# lion.net
KiCad netlist of a schematic drawn in EAGLE
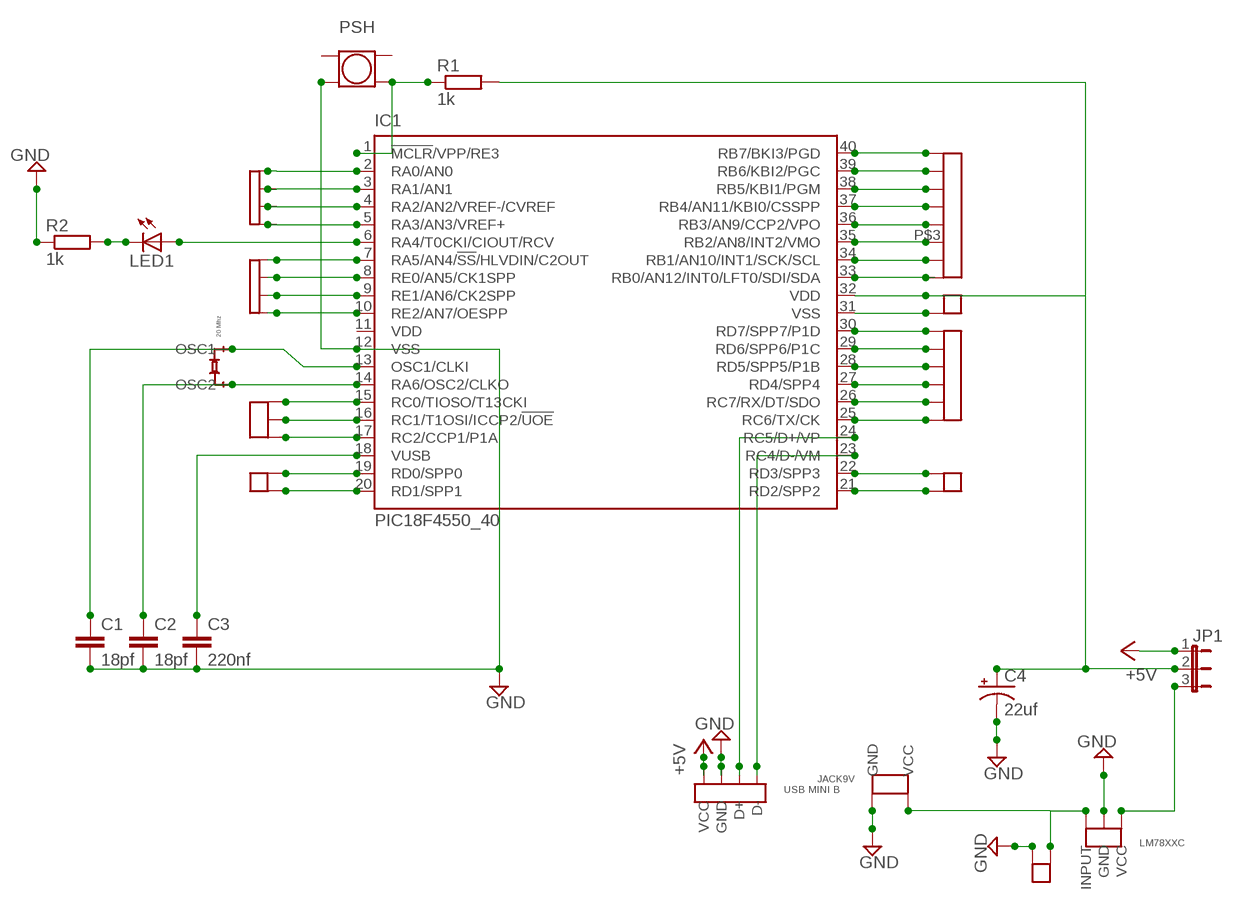
[diagram p0: schematic, sheet 1]

(export (version "E")
  (design (tool "Eeschema 10.0.6"))
  (components
    (comp (ref "BUTTON1")
      (value "PUSHBTN")
      (footprint "eagle-import:PUSHBTN")
      (libsource (lib "eagle-import") (part "PUSHBTN"))
    )
    (comp (ref "C1")
      (value "18pf")
      (footprint "eagle-import:C050-025X075")
      (libsource (lib "eagle-import") (part "C-EU050-025X075"))
    )
    (comp (ref "C2")
      (value "18pf")
      (footprint "eagle-import:C050-025X075")
      (libsource (lib "eagle-import") (part "C-EU050-025X075"))
    )
    (comp (ref "C3")
      (value "220nf")
      (footprint "eagle-import:C050-025X075")
      (libsource (lib "eagle-import") (part "C-EU050-025X075"))
    )
    (comp (ref "C4")
      (value "22uf")
      (footprint "eagle-import:E2,5-6E")
      (libsource (lib "eagle-import") (part "CPOL-USE2,5-6E"))
    )
    (comp (ref "IC1")
      (value "PIC18F4550_40")
      (footprint "eagle-import:DIL40")
      (fields (field (name "MF") "MICROCHIP") (field (name "MPN") "PIC18F4550-I/P"))
      (libsource (lib "eagle-import") (part "PIC18F4_40550"))
    )
    (comp (ref "JACK9V")
      (value "9VJACK")
      (footprint "eagle-import:9VJACK")
      (libsource (lib "eagle-import") (part "9VJACK"))
    )
    (comp (ref "JP1")
      (value "JP2E")
      (footprint "eagle-import:JP2")
      (libsource (lib "eagle-import") (part "JP2E"))
    )
    (comp (ref "LED1")
      (value "LEDLD260")
      (footprint "eagle-import:LD260")
      (libsource (lib "eagle-import") (part "LEDLD260"))
    )
    (comp (ref "R1")
      (value "1k")
      (footprint "eagle-import:0204_7")
      (libsource (lib "eagle-import") (part "R-EU_0204/7"))
    )
    (comp (ref "R2")
      (value "1k")
      (footprint "eagle-import:0204_7")
      (libsource (lib "eagle-import") (part "R-EU_0204/7"))
    )
    (comp (ref "U$1")
      (value "USBMINIB")
      (footprint "eagle-import:USBMINIB")
      (libsource (lib "eagle-import") (part "USBMINIB"))
    )
    (comp (ref "U$2")
      (value "20 Mhz")
      (footprint "eagle-import:CRYSTAL")
      (libsource (lib "eagle-import") (part "CRYSTAL"))
    )
    (comp (ref "U$3")
      (value "DUBOX3")
      (footprint "eagle-import:DUBOX3")
      (libsource (lib "eagle-import") (part "DUBOX3"))
    )
    (comp (ref "U$4")
      (value "DUBOX6")
      (footprint "eagle-import:DUBOX6")
      (libsource (lib "eagle-import") (part "DUBOX6"))
    )
    (comp (ref "U$5")
      (value "DUBOX8")
      (footprint "eagle-import:DUBOX8")
      (libsource (lib "eagle-import") (part "DUBOX8"))
    )
    (comp (ref "U$6")
      (value "DUBOX2")
      (footprint "eagle-import:DUBOX2")
      (libsource (lib "eagle-import") (part "DUBOX2"))
    )
    (comp (ref "U$7")
      (value "DUBOX2")
      (footprint "eagle-import:DUBOX2")
      (libsource (lib "eagle-import") (part "DUBOX2"))
    )
    (comp (ref "U$8")
      (value "DUBOX2")
      (footprint "eagle-import:DUBOX2")
      (libsource (lib "eagle-import") (part "DUBOX2"))
    )
    (comp (ref "U$9")
      (value "DUBOX4")
      (footprint "eagle-import:DUBOX4")
      (libsource (lib "eagle-import") (part "DUBOX4"))
    )
    (comp (ref "U$10")
      (value "DUBOX4")
      (footprint "eagle-import:DUBOX4")
      (libsource (lib "eagle-import") (part "DUBOX4"))
    )
    (comp (ref "U$11")
      (value "LM7805C")
      (footprint "eagle-import:LM7805C")
      (libsource (lib "eagle-import") (part "LM7805C"))
    )
    (comp (ref "U$12")
      (value "DUBOX2")
      (footprint "eagle-import:DUBOX2")
      (libsource (lib "eagle-import") (part "DUBOX2"))
    )
  )
  (nets
    (net (code "1") (name "+5V") (class "Default")
      (node (ref "JP1") (pin "1") (pinfunction "1_1") (pintype "passive"))
      (node (ref "U$1") (pin "VCC") (pinfunction "VCC_VCC") (pintype "power_in"))
    )
    (net (code "2") (name "/VDD") (class "Default")
      (node (ref "IC1") (pin "11") (pinfunction "VDD_11") (pintype "power_in"))
    )
    (net (code "3") (name "GND") (class "Default")
      (node (ref "BUTTON1") (pin "P$2") (pinfunction "P12_P$2") (pintype "bidirectional"))
      (node (ref "C1") (pin "2") (pinfunction "2_2") (pintype "passive"))
      (node (ref "C2") (pin "2") (pinfunction "2_2") (pintype "passive"))
      (node (ref "C3") (pin "2") (pinfunction "2_2") (pintype "passive"))
      (node (ref "C4") (pin "-") (pinfunction "-_-") (pintype "passive"))
      (node (ref "IC1") (pin "12") (pinfunction "VSS_12") (pintype "power_in"))
      (node (ref "JACK9V") (pin "GND") (pinfunction "GND_GND") (pintype "power_in"))
      (node (ref "R2") (pin "1") (pinfunction "1_1") (pintype "passive"))
      (node (ref "U$1") (pin "GND") (pinfunction "GND_GND") (pintype "power_in"))
      (node (ref "U$11") (pin "GND") (pinfunction "GND_GND") (pintype "power_in"))
      (node (ref "U$12") (pin "P$1") (pinfunction "P1_P$1") (pintype "bidirectional"))
    )
    (net (code "4") (name "Net-(BUTTON1-P22)") (class "Default")
      (node (ref "BUTTON1") (pin "P$4") (pinfunction "P22_P$4") (pintype "bidirectional"))
      (node (ref "IC1") (pin "1") (pinfunction "~{MCLR}/VPP/RE3_1") (pintype "input"))
      (node (ref "R1") (pin "1") (pinfunction "1_1") (pintype "passive"))
    )
    (net (code "5") (name "Net-(IC1-OSC1{slash}CLKI)") (class "Default")
      (node (ref "C1") (pin "1") (pinfunction "1_1") (pintype "passive"))
      (node (ref "IC1") (pin "13") (pinfunction "OSC1/CLKI_13") (pintype "input"))
      (node (ref "U$2") (pin "P$1") (pinfunction "OSC1_P$1") (pintype "bidirectional"))
    )
    (net (code "6") (name "Net-(IC1-RA0{slash}AN0)") (class "Default")
      (node (ref "IC1") (pin "2") (pinfunction "RA0/AN0_2") (pintype "bidirectional"))
      (node (ref "U$9") (pin "P$1") (pinfunction "P1_P$1") (pintype "bidirectional"))
    )
    (net (code "7") (name "Net-(IC1-RA1{slash}AN1)") (class "Default")
      (node (ref "IC1") (pin "3") (pinfunction "RA1/AN1_3") (pintype "bidirectional"))
      (node (ref "U$9") (pin "P$2") (pinfunction "P2_P$2") (pintype "bidirectional"))
    )
    (net (code "8") (name "Net-(IC1-RA2{slash}AN2{slash}VREF-{slash}CVREF)") (class "Default")
      (node (ref "IC1") (pin "4") (pinfunction "RA2/AN2/VREF-/CVREF_4") (pintype "bidirectional"))
      (node (ref "U$9") (pin "P$3") (pinfunction "P3_P$3") (pintype "bidirectional"))
    )
    (net (code "9") (name "Net-(IC1-RA3{slash}AN3{slash}VREF+)") (class "Default")
      (node (ref "IC1") (pin "5") (pinfunction "RA3/AN3/VREF+_5") (pintype "bidirectional"))
      (node (ref "U$9") (pin "P$4") (pinfunction "P4_P$4") (pintype "bidirectional"))
    )
    (net (code "10") (name "Net-(IC1-RA4{slash}T0CKI{slash}CIOUT{slash}RCV)") (class "Default")
      (node (ref "IC1") (pin "6") (pinfunction "RA4/T0CKI/CIOUT/RCV_6") (pintype "bidirectional"))
      (node (ref "LED1") (pin "A") (pinfunction "A_A") (pintype "passive"))
    )
    (net (code "11") (name "Net-(IC1-RA5{slash}AN4{slash}~{SS}{slash}HLVDIN{slash}C2OUT)") (class "Default")
      (node (ref "IC1") (pin "7") (pinfunction "RA5/AN4/~{SS}/HLVDIN/C2OUT_7") (pintype "bidirectional"))
      (node (ref "U$10") (pin "P$1") (pinfunction "P1_P$1") (pintype "bidirectional"))
    )
    (net (code "12") (name "Net-(IC1-RA6{slash}OSC2{slash}CLKO)") (class "Default")
      (node (ref "C2") (pin "1") (pinfunction "1_1") (pintype "passive"))
      (node (ref "IC1") (pin "14") (pinfunction "RA6/OSC2/CLKO_14") (pintype "output"))
      (node (ref "U$2") (pin "P$2") (pinfunction "OSC2_P$2") (pintype "bidirectional"))
    )
    (net (code "13") (name "Net-(IC1-RB0{slash}AN12{slash}INT0{slash}LFT0{slash}SDI{slash}SDA)") (class "Default")
      (node (ref "IC1") (pin "33") (pinfunction "RB0/AN12/INT0/LFT0/SDI/SDA_33") (pintype "bidirectional"))
      (node (ref "U$5") (pin "P$1") (pinfunction "P$1_P$1") (pintype "bidirectional"))
    )
    (net (code "14") (name "Net-(IC1-RB1{slash}AN10{slash}INT1{slash}SCK{slash}SCL)") (class "Default")
      (node (ref "IC1") (pin "34") (pinfunction "RB1/AN10/INT1/SCK/SCL_34") (pintype "bidirectional"))
      (node (ref "U$5") (pin "P$2") (pinfunction "P$2_P$2") (pintype "bidirectional"))
    )
    (net (code "15") (name "Net-(IC1-RB2{slash}AN8{slash}INT2{slash}VMO)") (class "Default")
      (node (ref "IC1") (pin "35") (pinfunction "RB2/AN8/INT2/VMO_35") (pintype "bidirectional"))
      (node (ref "U$5") (pin "P$3") (pinfunction "P$3_P$3") (pintype "bidirectional"))
    )
    (net (code "16") (name "Net-(IC1-RB3{slash}AN9{slash}CCP2{slash}VPO)") (class "Default")
      (node (ref "IC1") (pin "36") (pinfunction "RB3/AN9/CCP2/VPO_36") (pintype "bidirectional"))
      (node (ref "U$5") (pin "P$4") (pinfunction "P$4_P$4") (pintype "bidirectional"))
    )
    (net (code "17") (name "Net-(IC1-RB4{slash}AN11{slash}KBI0{slash}CSSPP)") (class "Default")
      (node (ref "IC1") (pin "37") (pinfunction "RB4/AN11/KBI0/CSSPP_37") (pintype "bidirectional"))
      (node (ref "U$5") (pin "P$5") (pinfunction "P$5_P$5") (pintype "bidirectional"))
    )
    (net (code "18") (name "Net-(IC1-RB5{slash}KBI1{slash}PGM)") (class "Default")
      (node (ref "IC1") (pin "38") (pinfunction "RB5/KBI1/PGM_38") (pintype "bidirectional"))
      (node (ref "U$5") (pin "P$6") (pinfunction "P$6_P$6") (pintype "bidirectional"))
    )
    (net (code "19") (name "Net-(IC1-RB6{slash}KBI2{slash}PGC)") (class "Default")
      (node (ref "IC1") (pin "39") (pinfunction "RB6/KBI2/PGC_39") (pintype "bidirectional"))
      (node (ref "U$5") (pin "P$7") (pinfunction "P$7_P$7") (pintype "bidirectional"))
    )
    (net (code "20") (name "Net-(IC1-RB7{slash}BKI3{slash}PGD)") (class "Default")
      (node (ref "IC1") (pin "40") (pinfunction "RB7/BKI3/PGD_40") (pintype "bidirectional"))
      (node (ref "U$5") (pin "P$8") (pinfunction "P$8_P$8") (pintype "bidirectional"))
    )
    (net (code "21") (name "Net-(IC1-RC0{slash}TIOSO{slash}T13CKI)") (class "Default")
      (node (ref "IC1") (pin "15") (pinfunction "RC0/TIOSO/T13CKI_15") (pintype "bidirectional"))
      (node (ref "U$3") (pin "P$1") (pinfunction "P$1_P$1") (pintype "bidirectional"))
    )
    (net (code "22") (name "Net-(IC1-RC1{slash}T1OSI{slash}ICCP2{slash}~{UOE})") (class "Default")
      (node (ref "IC1") (pin "16") (pinfunction "RC1/T1OSI/ICCP2/~{UOE}_16") (pintype "bidirectional"))
      (node (ref "U$3") (pin "P$2") (pinfunction "P$2_P$2") (pintype "bidirectional"))
    )
    (net (code "23") (name "Net-(IC1-RC2{slash}CCP1{slash}P1A)") (class "Default")
      (node (ref "IC1") (pin "17") (pinfunction "RC2/CCP1/P1A_17") (pintype "bidirectional"))
      (node (ref "U$3") (pin "P$3") (pinfunction "P$3_P$3") (pintype "bidirectional"))
    )
    (net (code "24") (name "Net-(IC1-RC4{slash}D-{slash}VM)") (class "Default")
      (node (ref "IC1") (pin "23") (pinfunction "RC4/D-/VM_23") (pintype "bidirectional"))
      (node (ref "U$1") (pin "D-") (pinfunction "D-_D-") (pintype "bidirectional"))
    )
    (net (code "25") (name "Net-(IC1-RC5{slash}D+{slash}VP)") (class "Default")
      (node (ref "IC1") (pin "24") (pinfunction "RC5/D+/VP_24") (pintype "bidirectional"))
      (node (ref "U$1") (pin "D+") (pinfunction "D+_D+") (pintype "bidirectional"))
    )
    (net (code "26") (name "Net-(IC1-RC6{slash}TX{slash}CK)") (class "Default")
      (node (ref "IC1") (pin "25") (pinfunction "RC6/TX/CK_25") (pintype "bidirectional"))
      (node (ref "U$4") (pin "P$1") (pinfunction "P$1_P$1") (pintype "bidirectional"))
    )
    (net (code "27") (name "Net-(IC1-RC7{slash}RX{slash}DT{slash}SDO)") (class "Default")
      (node (ref "IC1") (pin "26") (pinfunction "RC7/RX/DT/SDO_26") (pintype "bidirectional"))
      (node (ref "U$4") (pin "P$2") (pinfunction "P$2_P$2") (pintype "bidirectional"))
    )
    (net (code "28") (name "Net-(IC1-RD0{slash}SPP0)") (class "Default")
      (node (ref "IC1") (pin "19") (pinfunction "RD0/SPP0_19") (pintype "bidirectional"))
      (node (ref "U$6") (pin "P$1") (pinfunction "P1_P$1") (pintype "bidirectional"))
    )
    (net (code "29") (name "Net-(IC1-RD1{slash}SPP1)") (class "Default")
      (node (ref "IC1") (pin "20") (pinfunction "RD1/SPP1_20") (pintype "bidirectional"))
      (node (ref "U$6") (pin "P$2") (pinfunction "P2_P$2") (pintype "bidirectional"))
    )
    (net (code "30") (name "Net-(IC1-RD2{slash}SPP2)") (class "Default")
      (node (ref "IC1") (pin "21") (pinfunction "RD2/SPP2_21") (pintype "bidirectional"))
      (node (ref "U$8") (pin "P$1") (pinfunction "P1_P$1") (pintype "bidirectional"))
    )
    (net (code "31") (name "Net-(IC1-RD3{slash}SPP3)") (class "Default")
      (node (ref "IC1") (pin "22") (pinfunction "RD3/SPP3_22") (pintype "bidirectional"))
      (node (ref "U$8") (pin "P$2") (pinfunction "P2_P$2") (pintype "bidirectional"))
    )
    (net (code "32") (name "Net-(IC1-RD4{slash}SPP4)") (class "Default")
      (node (ref "IC1") (pin "27") (pinfunction "RD4/SPP4_27") (pintype "bidirectional"))
      (node (ref "U$4") (pin "P$3") (pinfunction "P$3_P$3") (pintype "bidirectional"))
    )
    (net (code "33") (name "Net-(IC1-RD5{slash}SPP5{slash}P1B)") (class "Default")
      (node (ref "IC1") (pin "28") (pinfunction "RD5/SPP5/P1B_28") (pintype "bidirectional"))
      (node (ref "U$4") (pin "P$4") (pinfunction "P$4_P$4") (pintype "bidirectional"))
    )
    (net (code "34") (name "Net-(IC1-RD6{slash}SPP6{slash}P1C)") (class "Default")
      (node (ref "IC1") (pin "29") (pinfunction "RD6/SPP6/P1C_29") (pintype "bidirectional"))
      (node (ref "U$4") (pin "P$5") (pinfunction "P$5_P$5") (pintype "bidirectional"))
    )
    (net (code "35") (name "Net-(IC1-RD7{slash}SPP7{slash}P1D)") (class "Default")
      (node (ref "IC1") (pin "30") (pinfunction "RD7/SPP7/P1D_30") (pintype "bidirectional"))
      (node (ref "U$4") (pin "P$6") (pinfunction "P$6_P$6") (pintype "bidirectional"))
    )
    (net (code "36") (name "Net-(IC1-RE0{slash}AN5{slash}CK1SPP)") (class "Default")
      (node (ref "IC1") (pin "8") (pinfunction "RE0/AN5/CK1SPP_8") (pintype "bidirectional"))
      (node (ref "U$10") (pin "P$2") (pinfunction "P2_P$2") (pintype "bidirectional"))
    )
    (net (code "37") (name "Net-(IC1-RE1{slash}AN6{slash}CK2SPP)") (class "Default")
      (node (ref "IC1") (pin "9") (pinfunction "RE1/AN6/CK2SPP_9") (pintype "bidirectional"))
      (node (ref "U$10") (pin "P$3") (pinfunction "P3_P$3") (pintype "bidirectional"))
    )
    (net (code "38") (name "Net-(IC1-RE2{slash}AN7{slash}OESPP)") (class "Default")
      (node (ref "IC1") (pin "10") (pinfunction "RE2/AN7/OESPP_10") (pintype "bidirectional"))
      (node (ref "U$10") (pin "P$4") (pinfunction "P4_P$4") (pintype "bidirectional"))
    )
    (net (code "39") (name "Net-(IC1-VUSB)") (class "Default")
      (node (ref "C3") (pin "1") (pinfunction "1_1") (pintype "passive"))
      (node (ref "IC1") (pin "18") (pinfunction "VUSB_18") (pintype "bidirectional"))
    )
    (net (code "40") (name "Net-(LED1-C)") (class "Default")
      (node (ref "LED1") (pin "K") (pinfunction "C_K") (pintype "passive"))
      (node (ref "R2") (pin "2") (pinfunction "2_2") (pintype "passive"))
    )
    (net (code "41") (name "Net-(U$7-P1)") (class "Default")
      (node (ref "IC1") (pin "31") (pinfunction "VSS_31") (pintype "power_in"))
      (node (ref "U$7") (pin "P$1") (pinfunction "P1_P$1") (pintype "bidirectional"))
    )
    (net (code "42") (name "Net-(U$7-P2)") (class "Default")
      (node (ref "C4") (pin "+") (pinfunction "+_+") (pintype "passive"))
      (node (ref "IC1") (pin "32") (pinfunction "VDD_32") (pintype "power_in"))
      (node (ref "JP1") (pin "2") (pinfunction "2_2") (pintype "passive"))
      (node (ref "R1") (pin "2") (pinfunction "2_2") (pintype "passive"))
      (node (ref "U$7") (pin "P$2") (pinfunction "P2_P$2") (pintype "bidirectional"))
    )
    (net (code "43") (name "Net-(U$11-VCC)") (class "Default")
      (node (ref "JP1") (pin "3") (pinfunction "3_3") (pintype "passive"))
      (node (ref "U$11") (pin "OUTPUT") (pinfunction "VCC_OUTPUT") (pintype "power_in"))
    )
    (net (code "44") (name "Net-(U$12-P2)") (class "Default")
      (node (ref "JACK9V") (pin "VCC") (pinfunction "VCC_VCC") (pintype "power_in"))
      (node (ref "U$11") (pin "INPUT") (pinfunction "INPUT_INPUT") (pintype "input"))
      (node (ref "U$12") (pin "P$2") (pinfunction "P2_P$2") (pintype "bidirectional"))
    )
    (net (code "45") (name "unconnected-(BUTTON1-P11-PadP$1)") (class "Default")
      (node (ref "BUTTON1") (pin "P$1") (pinfunction "P11_P$1") (pintype "bidirectional"))
    )
    (net (code "46") (name "unconnected-(BUTTON1-P21-PadP$3)") (class "Default")
      (node (ref "BUTTON1") (pin "P$3") (pinfunction "P21_P$3") (pintype "bidirectional"))
    )
  )
)
